# nClon_001.net
KiCad netlist of a schematic drawn in EAGLE
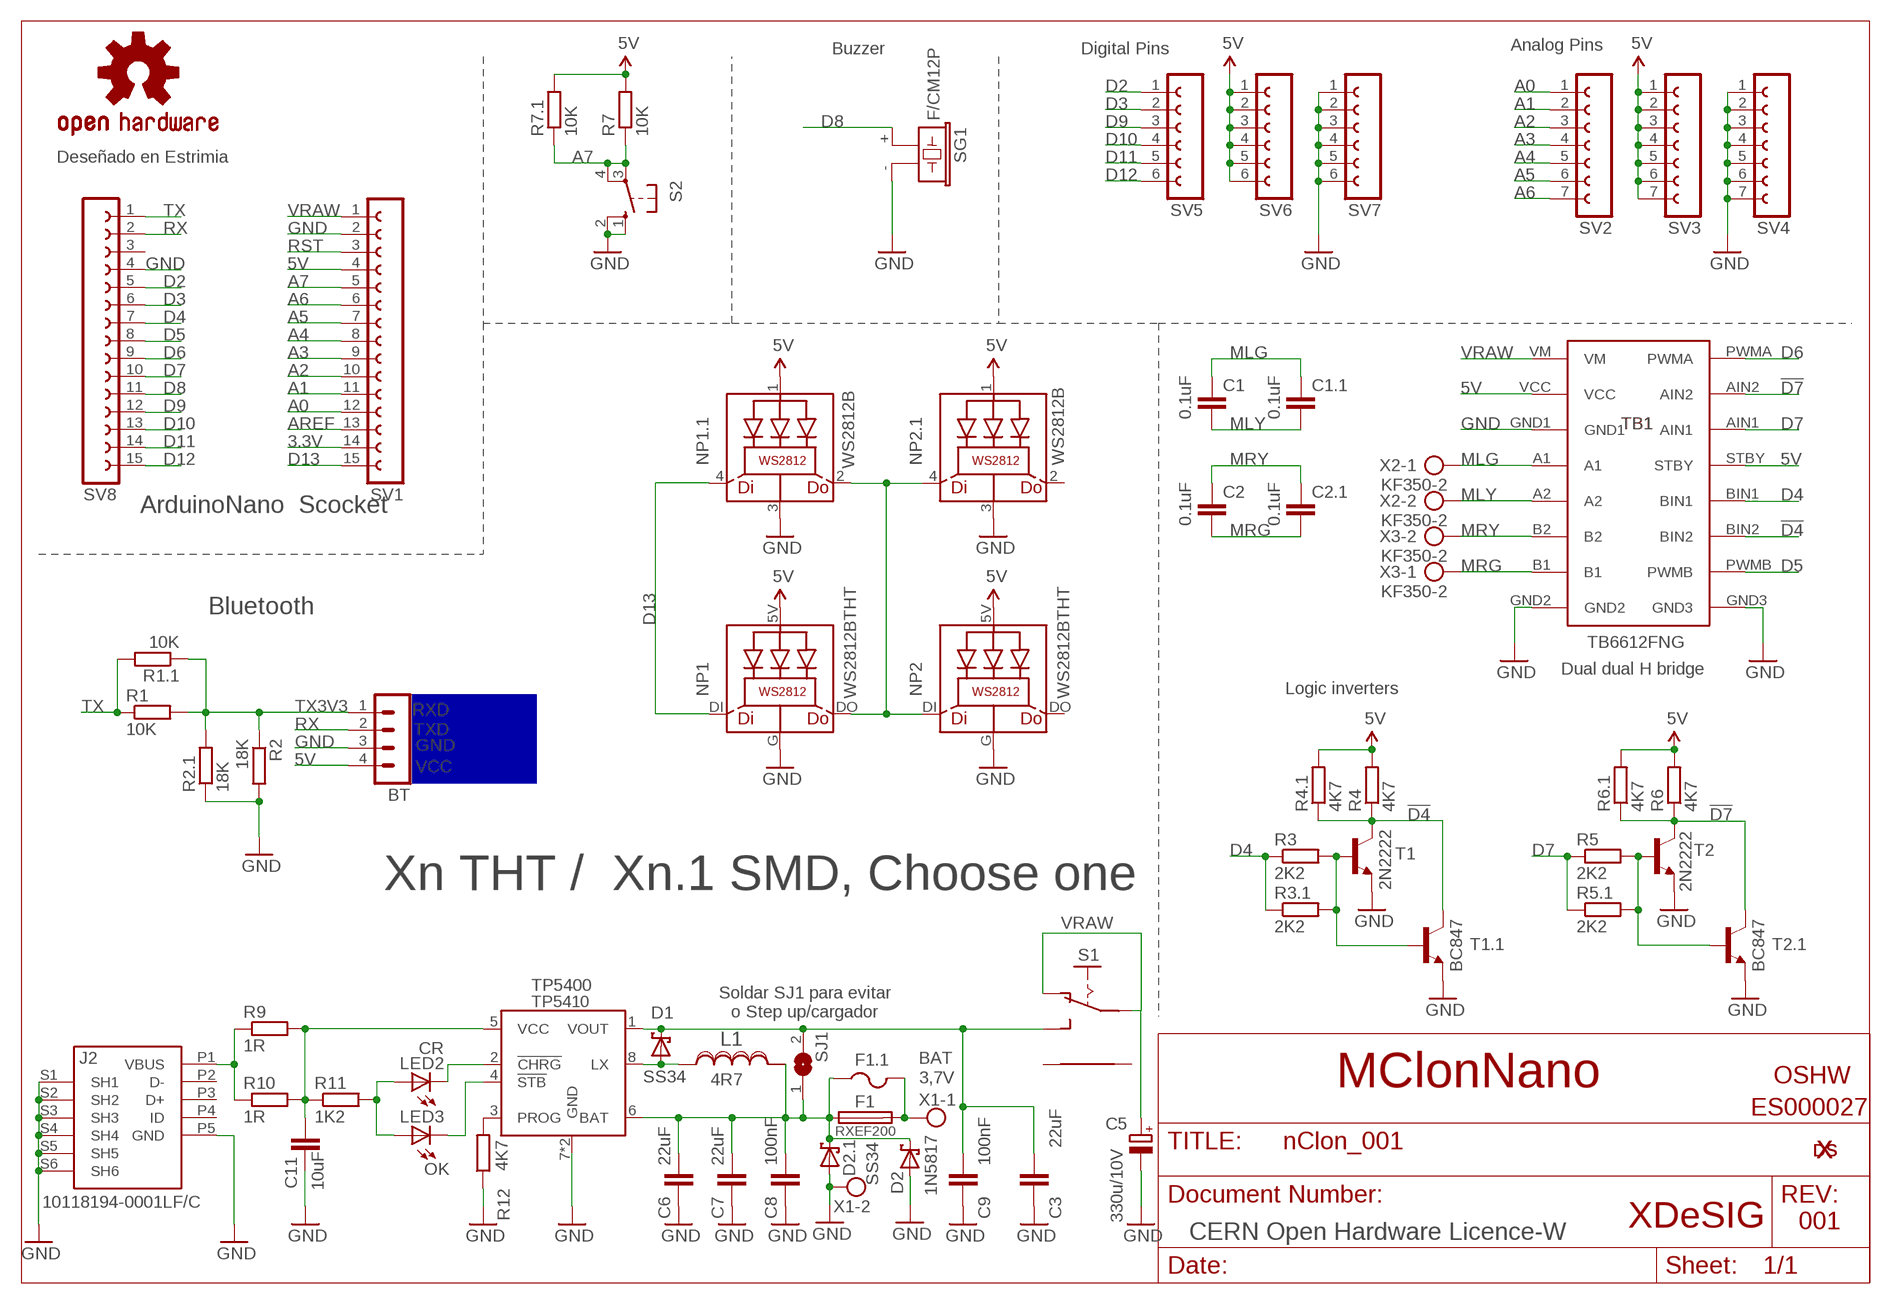
[diagram p0: schematic, sheet 1]

(export (version "E")
  (design (tool "Eeschema 10.0.6"))
  (components
    (comp (ref "BT")
      (value "MA04-1")
      (footprint "eagle-import:MA04-1")
      (libsource (lib "eagle-import") (part "MA04-1"))
    )
    (comp (ref "C1")
      (value "0.1uF")
      (footprint "eagle-import:C050-024X044")
      (libsource (lib "eagle-import") (part "C-EU050-024X044"))
    )
    (comp (ref "C1.1")
      (value "0.1uF")
      (footprint "eagle-import:C1206")
      (libsource (lib "eagle-import") (part "C-EUC1206"))
    )
    (comp (ref "C2")
      (value "0.1uF")
      (footprint "eagle-import:C050-024X044")
      (libsource (lib "eagle-import") (part "C-EU050-024X044"))
    )
    (comp (ref "C2.1")
      (value "0.1uF")
      (footprint "eagle-import:C1206")
      (libsource (lib "eagle-import") (part "C-EUC1206"))
    )
    (comp (ref "C3")
      (value "22uF")
      (footprint "eagle-import:C1206")
      (libsource (lib "eagle-import") (part "C-EUC1206"))
    )
    (comp (ref "C5")
      (value "330u/10V")
      (footprint "eagle-import:E2,5-6")
      (libsource (lib "eagle-import") (part "CPOL-EUE2.5-6"))
    )
    (comp (ref "C6")
      (value "22uF")
      (footprint "eagle-import:C1206")
      (libsource (lib "eagle-import") (part "C-EUC1206"))
    )
    (comp (ref "C7")
      (value "22uF")
      (footprint "eagle-import:C1206")
      (libsource (lib "eagle-import") (part "C-EUC1206"))
    )
    (comp (ref "C8")
      (value "100nF")
      (footprint "eagle-import:C1206")
      (libsource (lib "eagle-import") (part "C-EUC1206"))
    )
    (comp (ref "C9")
      (value "100nF")
      (footprint "eagle-import:C1206")
      (libsource (lib "eagle-import") (part "C-EUC1206"))
    )
    (comp (ref "C11")
      (value "10uF")
      (footprint "eagle-import:C1206")
      (libsource (lib "eagle-import") (part "C-EUC1206"))
    )
    (comp (ref "D1")
      (value "SS34")
      (footprint "eagle-import:DIODE_SMA")
      (libsource (lib "eagle-import") (part "DIODE_SCHOTTKY-DIODESMA"))
    )
    (comp (ref "D2")
      (value "1N5817")
      (footprint "eagle-import:DO35-7")
      (libsource (lib "eagle-import") (part "SCHOTTKY-DIODEDO35-7"))
    )
    (comp (ref "D2.1")
      (value "SS34")
      (footprint "eagle-import:DIODE_SMA")
      (libsource (lib "eagle-import") (part "DIODE_SCHOTTKY-DIODESMA"))
    )
    (comp (ref "F1")
      (value "RXEF200")
      (footprint "eagle-import:TE5")
      (libsource (lib "eagle-import") (part "FUSETE5"))
    )
    (comp (ref "F1.1")
      (value "MF-NSMF200")
      (footprint "eagle-import:1812")
      (libsource (lib "eagle-import") (part "PTCFUSE-1812"))
    )
    (comp (ref "J2")
      (value "10118194-0001LF/C")
      (footprint "eagle-import:SMARTPRJ_CON2_USB_MICRO_B_AT")
      (libsource (lib "eagle-import") (part "SMARTPRJ_MYCON2_USB-MINI-B"))
    )
    (comp (ref "L1")
      (value "4R7")
      (footprint "eagle-import:SRN6045")
      (fields (field (name "MF") "Bourns") (field (name "MP") "SRN6045-330M"))
      (libsource (lib "eagle-import") (part "SRN6045-330M6045"))
    )
    (comp (ref "LED2")
      (value "CR")
      (footprint "eagle-import:CHIPLED_0805")
      (libsource (lib "eagle-import") (part "LEDCHIPLED_0805"))
    )
    (comp (ref "LED3")
      (value "OK")
      (footprint "eagle-import:CHIPLED_0805")
      (libsource (lib "eagle-import") (part "LEDCHIPLED_0805"))
    )
    (comp (ref "LOGO4")
      (value "OSHW-LOGOS")
      (footprint "eagle-import:OSHW-LOGO-S")
      (libsource (lib "eagle-import") (part "OSHW-LOGOS"))
    )
    (comp (ref "NP1")
      (value "WS2812BTHT")
      (footprint "eagle-import:NEOPIXEL5MM")
      (libsource (lib "eagle-import") (part "WS2812BTHT"))
    )
    (comp (ref "NP1.1")
      (value "WS2812B")
      (footprint "eagle-import:5050-4")
      (libsource (lib "eagle-import") (part "WS2812B"))
    )
    (comp (ref "NP2")
      (value "WS2812BTHT")
      (footprint "eagle-import:NEOPIXEL5MM")
      (libsource (lib "eagle-import") (part "WS2812BTHT"))
    )
    (comp (ref "NP2.1")
      (value "WS2812B")
      (footprint "eagle-import:5050-4")
      (libsource (lib "eagle-import") (part "WS2812B"))
    )
    (comp (ref "R1")
      (value "10K")
      (footprint "eagle-import:0204_7")
      (libsource (lib "eagle-import") (part "R-EU_0204/7"))
    )
    (comp (ref "R1.1")
      (value "10K")
      (footprint "eagle-import:R1206")
      (libsource (lib "eagle-import") (part "R-EU_R1206"))
    )
    (comp (ref "R2")
      (value "18K")
      (footprint "eagle-import:0204_7")
      (libsource (lib "eagle-import") (part "R-EU_0204/7"))
    )
    (comp (ref "R2.1")
      (value "18K")
      (footprint "eagle-import:R1206")
      (libsource (lib "eagle-import") (part "R-EU_R1206"))
    )
    (comp (ref "R3")
      (value "2K2")
      (footprint "eagle-import:0204_7")
      (libsource (lib "eagle-import") (part "R-EU_0204/7"))
    )
    (comp (ref "R3.1")
      (value "2K2")
      (footprint "eagle-import:R1206")
      (libsource (lib "eagle-import") (part "R-EU_R1206"))
    )
    (comp (ref "R4")
      (value "4K7")
      (footprint "eagle-import:0204_7")
      (libsource (lib "eagle-import") (part "R-EU_0204/7"))
    )
    (comp (ref "R4.1")
      (value "4K7")
      (footprint "eagle-import:R1206")
      (libsource (lib "eagle-import") (part "R-EU_R1206"))
    )
    (comp (ref "R5")
      (value "2K2")
      (footprint "eagle-import:0204_7")
      (libsource (lib "eagle-import") (part "R-EU_0204/7"))
    )
    (comp (ref "R5.1")
      (value "2K2")
      (footprint "eagle-import:R1206")
      (libsource (lib "eagle-import") (part "R-EU_R1206"))
    )
    (comp (ref "R6")
      (value "4K7")
      (footprint "eagle-import:0204_7")
      (libsource (lib "eagle-import") (part "R-EU_0204/7"))
    )
    (comp (ref "R6.1")
      (value "4K7")
      (footprint "eagle-import:R1206")
      (libsource (lib "eagle-import") (part "R-EU_R1206"))
    )
    (comp (ref "R7")
      (value "10K")
      (footprint "eagle-import:0204_7")
      (libsource (lib "eagle-import") (part "R-EU_0204/7"))
    )
    (comp (ref "R7.1")
      (value "10K")
      (footprint "eagle-import:R1206")
      (libsource (lib "eagle-import") (part "R-EU_R1206"))
    )
    (comp (ref "R9")
      (value "1R")
      (footprint "eagle-import:M1206")
      (libsource (lib "eagle-import") (part "R-EU_M1206"))
    )
    (comp (ref "R10")
      (value "1R")
      (footprint "eagle-import:M1206")
      (libsource (lib "eagle-import") (part "R-EU_M1206"))
    )
    (comp (ref "R11")
      (value "1K2")
      (footprint "eagle-import:R1206")
      (libsource (lib "eagle-import") (part "R-EU_R1206"))
    )
    (comp (ref "R12")
      (value "4K7")
      (footprint "eagle-import:R1206")
      (libsource (lib "eagle-import") (part "R-EU_R1206"))
    )
    (comp (ref "S1")
      (value "ESCORNA_SK12F14D")
      (footprint "eagle-import:ESCORNA_SK-12D07")
      (libsource (lib "eagle-import") (part "ESCORNA_SK12F14D"))
    )
    (comp (ref "S2")
      (value "10-XX")
      (footprint "eagle-import:B3F-10XX")
      (fields (field (name "MPN") "B3F-1000"))
      (libsource (lib "eagle-import") (part "10-XX"))
    )
    (comp (ref "SG1")
      (value "F/CM12P")
      (footprint "eagle-import:F_CM12P")
      (libsource (lib "eagle-import") (part "F/CM12P"))
    )
    (comp (ref "SJ1")
      (value "JUMPER_SJW")
      (footprint "eagle-import:JUMPER_SJW")
      (libsource (lib "eagle-import") (part "JUMPER_SJW"))
    )
    (comp (ref "SV1")
      (value "CON-LSTA_FE15-1")
      (footprint "eagle-import:CON-LSTA_FE15")
      (libsource (lib "eagle-import") (part "CON-LSTA_FE15-1"))
    )
    (comp (ref "SV2")
      (value "FE07-1")
      (footprint "eagle-import:FE07")
      (libsource (lib "eagle-import") (part "FE07-1"))
    )
    (comp (ref "SV3")
      (value "FE07-1")
      (footprint "eagle-import:FE07")
      (libsource (lib "eagle-import") (part "FE07-1"))
    )
    (comp (ref "SV4")
      (value "FE07-1")
      (footprint "eagle-import:FE07")
      (libsource (lib "eagle-import") (part "FE07-1"))
    )
    (comp (ref "SV5")
      (value "FE06-1")
      (footprint "eagle-import:FE06")
      (libsource (lib "eagle-import") (part "FE06-1"))
    )
    (comp (ref "SV6")
      (value "FE06-1")
      (footprint "eagle-import:FE06")
      (libsource (lib "eagle-import") (part "FE06-1"))
    )
    (comp (ref "SV7")
      (value "FE06-1")
      (footprint "eagle-import:FE06")
      (libsource (lib "eagle-import") (part "FE06-1"))
    )
    (comp (ref "SV8")
      (value "CON-LSTA_FE15-1")
      (footprint "eagle-import:CON-LSTA_FE15")
      (libsource (lib "eagle-import") (part "CON-LSTA_FE15-1"))
    )
    (comp (ref "T1")
      (value "2N2222")
      (footprint "eagle-import:TO92-EBC-OVAL")
      (libsource (lib "eagle-import") (part "2N2222"))
    )
    (comp (ref "T1.1")
      (value "BC847")
      (footprint "eagle-import:SOT23")
      (libsource (lib "eagle-import") (part "BC847"))
    )
    (comp (ref "T2")
      (value "2N2222")
      (footprint "eagle-import:TO92-EBC-OVAL")
      (libsource (lib "eagle-import") (part "2N2222"))
    )
    (comp (ref "T2.1")
      (value "BC847")
      (footprint "eagle-import:SOT23")
      (libsource (lib "eagle-import") (part "BC847"))
    )
    (comp (ref "TB1")
      (value "TB6612FNG")
      (footprint "eagle-import:TB6612FNG")
      (libsource (lib "eagle-import") (part "TB6612FNG"))
    )
    (comp (ref "U$7")
      (value "OSHW")
      (footprint "eagle-import:OSHW")
      (libsource (lib "eagle-import") (part "OSHW"))
    )
    (comp (ref "U$8")
      (value "XDESIG5MM")
      (footprint "eagle-import:XDESIG_CU")
      (libsource (lib "eagle-import") (part "XDESIG5MM"))
    )
    (comp (ref "U$18")
      (value "XDESIG21")
      (footprint "eagle-import:XDESIG")
      (libsource (lib "eagle-import") (part "XDESIG21"))
    )
    (comp (ref "U$19")
      (value "XDESIG5MM")
      (footprint "eagle-import:XDESIG_CU")
      (libsource (lib "eagle-import") (part "XDESIG5MM"))
    )
    (comp (ref "U1")
      (value "TP5400")
      (footprint "eagle-import:ESOP8")
      (libsource (lib "eagle-import") (part "TP5400"))
    )
    (comp (ref "X1")
      (value "KF350-2")
      (footprint "eagle-import:AK550_2")
      (libsource (lib "eagle-import") (part "AK550/2"))
    )
    (comp (ref "X2")
      (value "KF350-2")
      (footprint "eagle-import:AK550_2")
      (libsource (lib "eagle-import") (part "AK550/2"))
    )
    (comp (ref "X3")
      (value "KF350-2")
      (footprint "eagle-import:AK550_2")
      (libsource (lib "eagle-import") (part "AK550/2"))
    )
  )
  (nets
    (net (code "1") (name "/3.3V") (class "Default")
      (node (ref "SV1") (pin "14") (pinfunction "14_14") (pintype "passive"))
    )
    (net (code "2") (name "/A0") (class "Default")
      (node (ref "SV1") (pin "12") (pinfunction "12_12") (pintype "passive"))
      (node (ref "SV2") (pin "1") (pinfunction "1_1") (pintype "passive"))
    )
    (net (code "3") (name "/A1") (class "Default")
      (node (ref "SV1") (pin "11") (pinfunction "11_11") (pintype "passive"))
      (node (ref "SV2") (pin "2") (pinfunction "2_2") (pintype "passive"))
    )
    (net (code "4") (name "/A2") (class "Default")
      (node (ref "SV1") (pin "10") (pinfunction "10_10") (pintype "passive"))
      (node (ref "SV2") (pin "3") (pinfunction "3_3") (pintype "passive"))
    )
    (net (code "5") (name "/A3") (class "Default")
      (node (ref "SV1") (pin "9") (pinfunction "9_9") (pintype "passive"))
      (node (ref "SV2") (pin "4") (pinfunction "4_4") (pintype "passive"))
    )
    (net (code "6") (name "/A4") (class "Default")
      (node (ref "SV1") (pin "8") (pinfunction "8_8") (pintype "passive"))
      (node (ref "SV2") (pin "5") (pinfunction "5_5") (pintype "passive"))
    )
    (net (code "7") (name "/A5") (class "Default")
      (node (ref "SV1") (pin "7") (pinfunction "7_7") (pintype "passive"))
      (node (ref "SV2") (pin "6") (pinfunction "6_6") (pintype "passive"))
    )
    (net (code "8") (name "/A6") (class "Default")
      (node (ref "SV1") (pin "6") (pinfunction "6_6") (pintype "passive"))
      (node (ref "SV2") (pin "7") (pinfunction "7_7") (pintype "passive"))
    )
    (net (code "9") (name "/A7") (class "Default")
      (node (ref "R7") (pin "1") (pinfunction "1_1") (pintype "passive"))
      (node (ref "R7.1") (pin "1") (pinfunction "1_1") (pintype "passive"))
      (node (ref "S2") (pin "3") (pinfunction "P_3") (pintype "passive"))
      (node (ref "S2") (pin "4") (pinfunction "P1_4") (pintype "passive"))
      (node (ref "SV1") (pin "5") (pinfunction "5_5") (pintype "passive"))
    )
    (net (code "10") (name "/AREF") (class "Default")
      (node (ref "SV1") (pin "13") (pinfunction "13_13") (pintype "passive"))
    )
    (net (code "11") (name "/BAT") (class "Default")
      (node (ref "C6") (pin "1") (pinfunction "1_1") (pintype "passive"))
      (node (ref "C7") (pin "1") (pinfunction "1_1") (pintype "passive"))
      (node (ref "C8") (pin "1") (pinfunction "1_1") (pintype "passive"))
      (node (ref "D2") (pin "C") (pinfunction "C_C") (pintype "passive"))
      (node (ref "D2.1") (pin "C") (pinfunction "C_C") (pintype "passive"))
      (node (ref "F1") (pin "1") (pinfunction "1_1") (pintype "passive"))
      (node (ref "F1.1") (pin "1") (pinfunction "1_1") (pintype "passive"))
      (node (ref "L1") (pin "1") (pinfunction "1_1") (pintype "passive"))
      (node (ref "SJ1") (pin "1") (pinfunction "1_1") (pintype "passive"))
      (node (ref "U1") (pin "6") (pinfunction "BAT_6") (pintype "bidirectional"))
    )
    (net (code "12") (name "/D2") (class "Default")
      (node (ref "SV5") (pin "1") (pinfunction "1_1") (pintype "passive"))
      (node (ref "SV8") (pin "5") (pinfunction "5_5") (pintype "passive"))
    )
    (net (code "13") (name "/D3") (class "Default")
      (node (ref "SV5") (pin "2") (pinfunction "2_2") (pintype "passive"))
      (node (ref "SV8") (pin "6") (pinfunction "6_6") (pintype "passive"))
    )
    (net (code "14") (name "/D4") (class "Default")
      (node (ref "R3") (pin "1") (pinfunction "1_1") (pintype "passive"))
      (node (ref "R3.1") (pin "1") (pinfunction "1_1") (pintype "passive"))
      (node (ref "SV8") (pin "7") (pinfunction "7_7") (pintype "passive"))
      (node (ref "TB1") (pin "BIN1") (pinfunction "BIN1_BIN1") (pintype "bidirectional"))
    )
    (net (code "15") (name "/D5") (class "Default")
      (node (ref "SV8") (pin "8") (pinfunction "8_8") (pintype "passive"))
      (node (ref "TB1") (pin "PWMB") (pinfunction "PWMB_PWMB") (pintype "bidirectional"))
    )
    (net (code "16") (name "/D6") (class "Default")
      (node (ref "SV8") (pin "9") (pinfunction "9_9") (pintype "passive"))
      (node (ref "TB1") (pin "PWMA") (pinfunction "PWMA_PWMA") (pintype "bidirectional"))
    )
    (net (code "17") (name "/D7") (class "Default")
      (node (ref "R5") (pin "1") (pinfunction "1_1") (pintype "passive"))
      (node (ref "R5.1") (pin "1") (pinfunction "1_1") (pintype "passive"))
      (node (ref "SV8") (pin "10") (pinfunction "10_10") (pintype "passive"))
      (node (ref "TB1") (pin "AIN1") (pinfunction "AIN1_AIN1") (pintype "bidirectional"))
    )
    (net (code "18") (name "/D8") (class "Default")
      (node (ref "SG1") (pin "+") (pinfunction "1_+") (pintype "passive"))
      (node (ref "SV8") (pin "11") (pinfunction "11_11") (pintype "passive"))
    )
    (net (code "19") (name "/D9") (class "Default")
      (node (ref "SV5") (pin "3") (pinfunction "3_3") (pintype "passive"))
      (node (ref "SV8") (pin "12") (pinfunction "12_12") (pintype "passive"))
    )
    (net (code "20") (name "/D10") (class "Default")
      (node (ref "SV5") (pin "4") (pinfunction "4_4") (pintype "passive"))
      (node (ref "SV8") (pin "13") (pinfunction "13_13") (pintype "passive"))
    )
    (net (code "21") (name "/D11") (class "Default")
      (node (ref "SV5") (pin "5") (pinfunction "5_5") (pintype "passive"))
      (node (ref "SV8") (pin "14") (pinfunction "14_14") (pintype "passive"))
    )
    (net (code "22") (name "/D12") (class "Default")
      (node (ref "SV5") (pin "6") (pinfunction "6_6") (pintype "passive"))
      (node (ref "SV8") (pin "15") (pinfunction "15_15") (pintype "passive"))
    )
    (net (code "23") (name "/D13") (class "Default")
      (node (ref "NP1") (pin "DI") (pinfunction "DI_DI") (pintype "input"))
      (node (ref "NP1.1") (pin "4") (pinfunction "DI_4") (pintype "input"))
      (node (ref "SV1") (pin "15") (pinfunction "15_15") (pintype "passive"))
    )
    (net (code "24") (name "/MLG") (class "Default")
      (node (ref "C1") (pin "1") (pinfunction "1_1") (pintype "passive"))
      (node (ref "C1.1") (pin "1") (pinfunction "1_1") (pintype "passive"))
      (node (ref "TB1") (pin "A1") (pinfunction "A1_A1") (pintype "bidirectional"))
      (node (ref "X2") (pin "1") (pinfunction "KL_1") (pintype "passive"))
    )
    (net (code "25") (name "/MLY") (class "Default")
      (node (ref "C1") (pin "2") (pinfunction "2_2") (pintype "passive"))
      (node (ref "C1.1") (pin "2") (pinfunction "2_2") (pintype "passive"))
      (node (ref "TB1") (pin "A2") (pinfunction "A2_A2") (pintype "bidirectional"))
      (node (ref "X2") (pin "2") (pinfunction "KL_2") (pintype "passive"))
    )
    (net (code "26") (name "/MRG") (class "Default")
      (node (ref "C2") (pin "2") (pinfunction "2_2") (pintype "passive"))
      (node (ref "C2.1") (pin "2") (pinfunction "2_2") (pintype "passive"))
      (node (ref "TB1") (pin "B1") (pinfunction "B1_B1") (pintype "bidirectional"))
      (node (ref "X3") (pin "1") (pinfunction "KL_1") (pintype "passive"))
    )
    (net (code "27") (name "/MRY") (class "Default")
      (node (ref "C2") (pin "1") (pinfunction "1_1") (pintype "passive"))
      (node (ref "C2.1") (pin "1") (pinfunction "1_1") (pintype "passive"))
      (node (ref "TB1") (pin "B2") (pinfunction "B2_B2") (pintype "bidirectional"))
      (node (ref "X3") (pin "2") (pinfunction "KL_2") (pintype "passive"))
    )
    (net (code "28") (name "/RST") (class "Default")
      (node (ref "SV1") (pin "3") (pinfunction "3_3") (pintype "passive"))
    )
    (net (code "29") (name "/RX") (class "Default")
      (node (ref "BT") (pin "2") (pinfunction "2_2") (pintype "passive"))
      (node (ref "SV8") (pin "2") (pinfunction "2_2") (pintype "passive"))
    )
    (net (code "30") (name "/TX") (class "Default")
      (node (ref "R1") (pin "1") (pinfunction "1_1") (pintype "passive"))
      (node (ref "R1.1") (pin "2") (pinfunction "2_2") (pintype "passive"))
      (node (ref "SV8") (pin "1") (pinfunction "1_1") (pintype "passive"))
    )
    (net (code "31") (name "/TX3V3") (class "Default")
      (node (ref "BT") (pin "1") (pinfunction "1_1") (pintype "passive"))
      (node (ref "R1") (pin "2") (pinfunction "2_2") (pintype "passive"))
      (node (ref "R1.1") (pin "1") (pinfunction "1_1") (pintype "passive"))
      (node (ref "R2") (pin "1") (pinfunction "1_1") (pintype "passive"))
      (node (ref "R2.1") (pin "2") (pinfunction "2_2") (pintype "passive"))
    )
    (net (code "32") (name "/VBUS") (class "Default")
      (node (ref "J2") (pin "P1") (pinfunction "VBUS_P1") (pintype "power_in"))
      (node (ref "R10") (pin "1") (pinfunction "1_1") (pintype "passive"))
      (node (ref "R9") (pin "1") (pinfunction "1_1") (pintype "passive"))
    )
    (net (code "33") (name "/VRAW") (class "Default")
      (node (ref "C5") (pin "+") (pinfunction "+_+") (pintype "passive"))
      (node (ref "S1") (pin "P$1") (pinfunction "P_P$1") (pintype "passive"))
      (node (ref "S1") (pin "P$2") (pinfunction "O_P$2") (pintype "passive"))
      (node (ref "SV1") (pin "1") (pinfunction "1_1") (pintype "passive"))
      (node (ref "TB1") (pin "VM") (pinfunction "VM_VM") (pintype "bidirectional"))
    )
    (net (code "34") (name "/~{D4}") (class "Default")
      (node (ref "R4") (pin "1") (pinfunction "1_1") (pintype "passive"))
      (node (ref "R4.1") (pin "1") (pinfunction "1_1") (pintype "passive"))
      (node (ref "T1") (pin "C") (pinfunction "C_C") (pintype "passive"))
      (node (ref "T1.1") (pin "3") (pinfunction "C_3") (pintype "passive"))
      (node (ref "TB1") (pin "BIN2") (pinfunction "BIN2_BIN2") (pintype "bidirectional"))
    )
    (net (code "35") (name "/~{D7}") (class "Default")
      (node (ref "R6") (pin "1") (pinfunction "1_1") (pintype "passive"))
      (node (ref "R6.1") (pin "1") (pinfunction "1_1") (pintype "passive"))
      (node (ref "T2") (pin "C") (pinfunction "C_C") (pintype "passive"))
      (node (ref "T2.1") (pin "3") (pinfunction "C_3") (pintype "passive"))
      (node (ref "TB1") (pin "AIN2") (pinfunction "AIN2_AIN2") (pintype "bidirectional"))
    )
    (net (code "36") (name "5V") (class "Default")
      (node (ref "BT") (pin "4") (pinfunction "4_4") (pintype "passive"))
      (node (ref "NP1") (pin "5V") (pinfunction "LEDVDD_5V") (pintype "power_in"))
      (node (ref "NP1.1") (pin "1") (pinfunction "LEDVDD_1") (pintype "power_in"))
      (node (ref "NP2") (pin "5V") (pinfunction "LEDVDD_5V") (pintype "power_in"))
      (node (ref "NP2.1") (pin "1") (pinfunction "LEDVDD_1") (pintype "power_in"))
      (node (ref "R4") (pin "2") (pinfunction "2_2") (pintype "passive"))
      (node (ref "R4.1") (pin "2") (pinfunction "2_2") (pintype "passive"))
      (node (ref "R6") (pin "2") (pinfunction "2_2") (pintype "passive"))
      (node (ref "R6.1") (pin "2") (pinfunction "2_2") (pintype "passive"))
      (node (ref "R7") (pin "2") (pinfunction "2_2") (pintype "passive"))
      (node (ref "R7.1") (pin "2") (pinfunction "2_2") (pintype "passive"))
      (node (ref "SV1") (pin "4") (pinfunction "4_4") (pintype "passive"))
      (node (ref "SV3") (pin "1") (pinfunction "1_1") (pintype "passive"))
      (node (ref "SV3") (pin "2") (pinfunction "2_2") (pintype "passive"))
      (node (ref "SV3") (pin "3") (pinfunction "3_3") (pintype "passive"))
      (node (ref "SV3") (pin "4") (pinfunction "4_4") (pintype "passive"))
      (node (ref "SV3") (pin "5") (pinfunction "5_5") (pintype "passive"))
      (node (ref "SV3") (pin "6") (pinfunction "6_6") (pintype "passive"))
      (node (ref "SV3") (pin "7") (pinfunction "7_7") (pintype "passive"))
      (node (ref "SV6") (pin "1") (pinfunction "1_1") (pintype "passive"))
      (node (ref "SV6") (pin "2") (pinfunction "2_2") (pintype "passive"))
      (node (ref "SV6") (pin "3") (pinfunction "3_3") (pintype "passive"))
      (node (ref "SV6") (pin "4") (pinfunction "4_4") (pintype "passive"))
      (node (ref "SV6") (pin "5") (pinfunction "5_5") (pintype "passive"))
      (node (ref "SV6") (pin "6") (pinfunction "6_6") (pintype "passive"))
      (node (ref "TB1") (pin "STBY") (pinfunction "STBY_STBY") (pintype "bidirectional"))
      (node (ref "TB1") (pin "VCC") (pinfunction "VCC_VCC") (pintype "bidirectional"))
    )
    (net (code "37") (name "GND") (class "Default")
      (node (ref "BT") (pin "3") (pinfunction "3_3") (pintype "passive"))
      (node (ref "C11") (pin "2") (pinfunction "2_2") (pintype "passive"))
      (node (ref "C3") (pin "2") (pinfunction "2_2") (pintype "passive"))
      (node (ref "C5") (pin "-") (pinfunction "-_-") (pintype "passive"))
      (node (ref "C6") (pin "2") (pinfunction "2_2") (pintype "passive"))
      (node (ref "C7") (pin "2") (pinfunction "2_2") (pintype "passive"))
      (node (ref "C8") (pin "2") (pinfunction "2_2") (pintype "passive"))
      (node (ref "C9") (pin "2") (pinfunction "2_2") (pintype "passive"))
      (node (ref "D2") (pin "A") (pinfunction "A_A") (pintype "passive"))
      (node (ref "D2.1") (pin "A") (pinfunction "A_A") (pintype "passive"))
      (node (ref "J2") (pin "P5") (pinfunction "GND_P5") (pintype "passive"))
      (node (ref "J2") (pin "S1") (pinfunction "SH1_S1") (pintype "passive"))
      (node (ref "J2") (pin "S2") (pinfunction "SH2_S2") (pintype "passive"))
      (node (ref "J2") (pin "S3") (pinfunction "SH3_S3") (pintype "passive"))
      (node (ref "J2") (pin "S4") (pinfunction "SH4_S4") (pintype "passive"))
      (node (ref "J2") (pin "S5") (pinfunction "SH5_S5") (pintype "passive"))
      (node (ref "J2") (pin "S6") (pinfunction "SH6_S6") (pintype "passive"))
      (node (ref "NP1") (pin "G") (pinfunction "GND_G") (pintype "power_in"))
      (node (ref "NP1.1") (pin "3") (pinfunction "GND_3") (pintype "power_in"))
      (node (ref "NP2") (pin "G") (pinfunction "GND_G") (pintype "power_in"))
      (node (ref "NP2.1") (pin "3") (pinfunction "GND_3") (pintype "power_in"))
      (node (ref "R12") (pin "1") (pinfunction "1_1") (pintype "passive"))
      (node (ref "R2") (pin "2") (pinfunction "2_2") (pintype "passive"))
      (node (ref "R2.1") (pin "1") (pinfunction "1_1") (pintype "passive"))
      (node (ref "S2") (pin "1") (pinfunction "S_1") (pintype "passive"))
      (node (ref "S2") (pin "2") (pinfunction "S1_2") (pintype "passive"))
      (node (ref "SG1") (pin "-") (pinfunction "2_-") (pintype "passive"))
      (node (ref "SV1") (pin "2") (pinfunction "2_2") (pintype "passive"))
      (node (ref "SV4") (pin "1") (pinfunction "1_1") (pintype "passive"))
      (node (ref "SV4") (pin "2") (pinfunction "2_2") (pintype "passive"))
      (node (ref "SV4") (pin "3") (pinfunction "3_3") (pintype "passive"))
      (node (ref "SV4") (pin "4") (pinfunction "4_4") (pintype "passive"))
      (node (ref "SV4") (pin "5") (pinfunction "5_5") (pintype "passive"))
      (node (ref "SV4") (pin "6") (pinfunction "6_6") (pintype "passive"))
      (node (ref "SV4") (pin "7") (pinfunction "7_7") (pintype "passive"))
      (node (ref "SV7") (pin "1") (pinfunction "1_1") (pintype "passive"))
      (node (ref "SV7") (pin "2") (pinfunction "2_2") (pintype "passive"))
      (node (ref "SV7") (pin "3") (pinfunction "3_3") (pintype "passive"))
      (node (ref "SV7") (pin "4") (pinfunction "4_4") (pintype "passive"))
      (node (ref "SV7") (pin "5") (pinfunction "5_5") (pintype "passive"))
      (node (ref "SV7") (pin "6") (pinfunction "6_6") (pintype "passive"))
      (node (ref "SV8") (pin "4") (pinfunction "4_4") (pintype "passive"))
      (node (ref "T1") (pin "E") (pinfunction "E_E") (pintype "passive"))
      (node (ref "T1.1") (pin "2") (pinfunction "E_2") (pintype "passive"))
      (node (ref "T2") (pin "E") (pinfunction "E_E") (pintype "passive"))
      (node (ref "T2.1") (pin "2") (pinfunction "E_2") (pintype "passive"))
      (node (ref "TB1") (pin "GND1") (pinfunction "GND1_GND1") (pintype "bidirectional"))
      (node (ref "TB1") (pin "GND2") (pinfunction "GND2_GND2") (pintype "bidirectional"))
      (node (ref "TB1") (pin "GND3") (pinfunction "GND3_GND3") (pintype "bidirectional"))
      (node (ref "U1") (pin "7") (pinfunction "GND_7") (pintype "power_in"))
      (node (ref "U1") (pin "9") (pinfunction "GND_9") (pintype "power_in"))
      (node (ref "X1") (pin "2") (pinfunction "KL_2") (pintype "passive"))
    )
    (net (code "38") (name "Net-(LED2-PadA)") (class "Default")
      (node (ref "LED2") (pin "A") (pinfunction "A_A") (pintype "passive"))
      (node (ref "LED3") (pin "A") (pinfunction "A_A") (pintype "passive"))
      (node (ref "R11") (pin "2") (pinfunction "2_2") (pintype "passive"))
    )
    (net (code "39") (name "Net-(NP1.1-DO)") (class "Default")
      (node (ref "NP1") (pin "DO") (pinfunction "DO_DO") (pintype "output"))
      (node (ref "NP1.1") (pin "2") (pinfunction "DO_2") (pintype "output"))
      (node (ref "NP2") (pin "DI") (pinfunction "DI_DI") (pintype "input"))
      (node (ref "NP2.1") (pin "4") (pinfunction "DI_4") (pintype "input"))
    )
    (net (code "40") (name "Net-(S1-S)") (class "Default")
      (node (ref "C3") (pin "1") (pinfunction "1_1") (pintype "passive"))
      (node (ref "C9") (pin "1") (pinfunction "1_1") (pintype "passive"))
      (node (ref "D1") (pin "C") (pinfunction "C_C") (pintype "passive"))
      (node (ref "S1") (pin "P$3") (pinfunction "S_P$3") (pintype "passive"))
      (node (ref "SJ1") (pin "2") (pinfunction "2_2") (pintype "passive"))
      (node (ref "U1") (pin "1") (pinfunction "VOUT_1") (pintype "power_in"))
    )
    (net (code "41") (name "Net-(T1.1-B)") (class "Default")
      (node (ref "R3") (pin "2") (pinfunction "2_2") (pintype "passive"))
      (node (ref "R3.1") (pin "2") (pinfunction "2_2") (pintype "passive"))
      (node (ref "T1") (pin "B") (pinfunction "B_B") (pintype "passive"))
      (node (ref "T1.1") (pin "1") (pinfunction "B_1") (pintype "passive"))
    )
    (net (code "42") (name "Net-(T2.1-B)") (class "Default")
      (node (ref "R5") (pin "2") (pinfunction "2_2") (pintype "passive"))
      (node (ref "R5.1") (pin "2") (pinfunction "2_2") (pintype "passive"))
      (node (ref "T2") (pin "B") (pinfunction "B_B") (pintype "passive"))
      (node (ref "T2.1") (pin "1") (pinfunction "B_1") (pintype "passive"))
    )
    (net (code "43") (name "Net-(U1-LX)") (class "Default")
      (node (ref "D1") (pin "A") (pinfunction "A_A") (pintype "passive"))
      (node (ref "L1") (pin "2") (pinfunction "2_2") (pintype "passive"))
      (node (ref "U1") (pin "8") (pinfunction "LX_8") (pintype "bidirectional"))
    )
    (net (code "44") (name "Net-(U1-PROG)") (class "Default")
      (node (ref "R12") (pin "2") (pinfunction "2_2") (pintype "passive"))
      (node (ref "U1") (pin "3") (pinfunction "PROG_3") (pintype "bidirectional"))
    )
    (net (code "45") (name "Net-(U1-VCC)") (class "Default")
      (node (ref "C11") (pin "1") (pinfunction "1_1") (pintype "passive"))
      (node (ref "R10") (pin "2") (pinfunction "2_2") (pintype "passive"))
      (node (ref "R11") (pin "1") (pinfunction "1_1") (pintype "passive"))
      (node (ref "R9") (pin "2") (pinfunction "2_2") (pintype "passive"))
      (node (ref "U1") (pin "5") (pinfunction "VCC_5") (pintype "power_in"))
    )
    (net (code "46") (name "Net-(U1-~{CHRG})") (class "Default")
      (node (ref "LED2") (pin "C") (pinfunction "C_C") (pintype "passive"))
      (node (ref "U1") (pin "2") (pinfunction "~{CHRG}_2") (pintype "bidirectional"))
    )
    (net (code "47") (name "Net-(U1-~{STB})") (class "Default")
      (node (ref "LED3") (pin "C") (pinfunction "C_C") (pintype "passive"))
      (node (ref "U1") (pin "4") (pinfunction "~{STB}_4") (pintype "bidirectional"))
    )
    (net (code "48") (name "Net-(X1A-KL)") (class "Default")
      (node (ref "F1") (pin "2") (pinfunction "2_2") (pintype "passive"))
      (node (ref "F1.1") (pin "2") (pinfunction "2_2") (pintype "passive"))
      (node (ref "X1") (pin "1") (pinfunction "KL_1") (pintype "passive"))
    )
    (net (code "49") (name "unconnected-(J2-D+-PadP3)") (class "Default")
      (node (ref "J2") (pin "P3") (pinfunction "D+_P3") (pintype "bidirectional"))
    )
    (net (code "50") (name "unconnected-(J2-D--PadP2)") (class "Default")
      (node (ref "J2") (pin "P2") (pinfunction "D-_P2") (pintype "bidirectional"))
    )
    (net (code "51") (name "unconnected-(J2-ID-PadP4)") (class "Default")
      (node (ref "J2") (pin "P4") (pinfunction "ID_P4") (pintype "bidirectional"))
    )
    (net (code "52") (name "unconnected-(NP2-PadDO)") (class "Default")
      (node (ref "NP2") (pin "DO") (pinfunction "DO_DO") (pintype "output"))
    )
    (net (code "53") (name "unconnected-(NP2.1-DO-Pad2)") (class "Default")
      (node (ref "NP2.1") (pin "2") (pinfunction "DO_2") (pintype "output"))
    )
    (net (code "54") (name "unconnected-(S1-P$1-PadP$4)") (class "Default")
      (node (ref "S1") (pin "P$4") (pinfunction "P$1_P$4") (pintype "passive"))
    )
    (net (code "55") (name "unconnected-(S1-P$2-PadP$5)") (class "Default")
      (node (ref "S1") (pin "P$5") (pinfunction "P$2_P$5") (pintype "bidirectional"))
    )
    (net (code "56") (name "unconnected-(SV8-Pad3)") (class "Default")
      (node (ref "SV8") (pin "3") (pinfunction "3_3") (pintype "passive"))
    )
  )
)
